# SCH_LucidVR_Proto5_SensorModule_RevB.net
KiCad netlist of a schematic drawn in EasyEDA
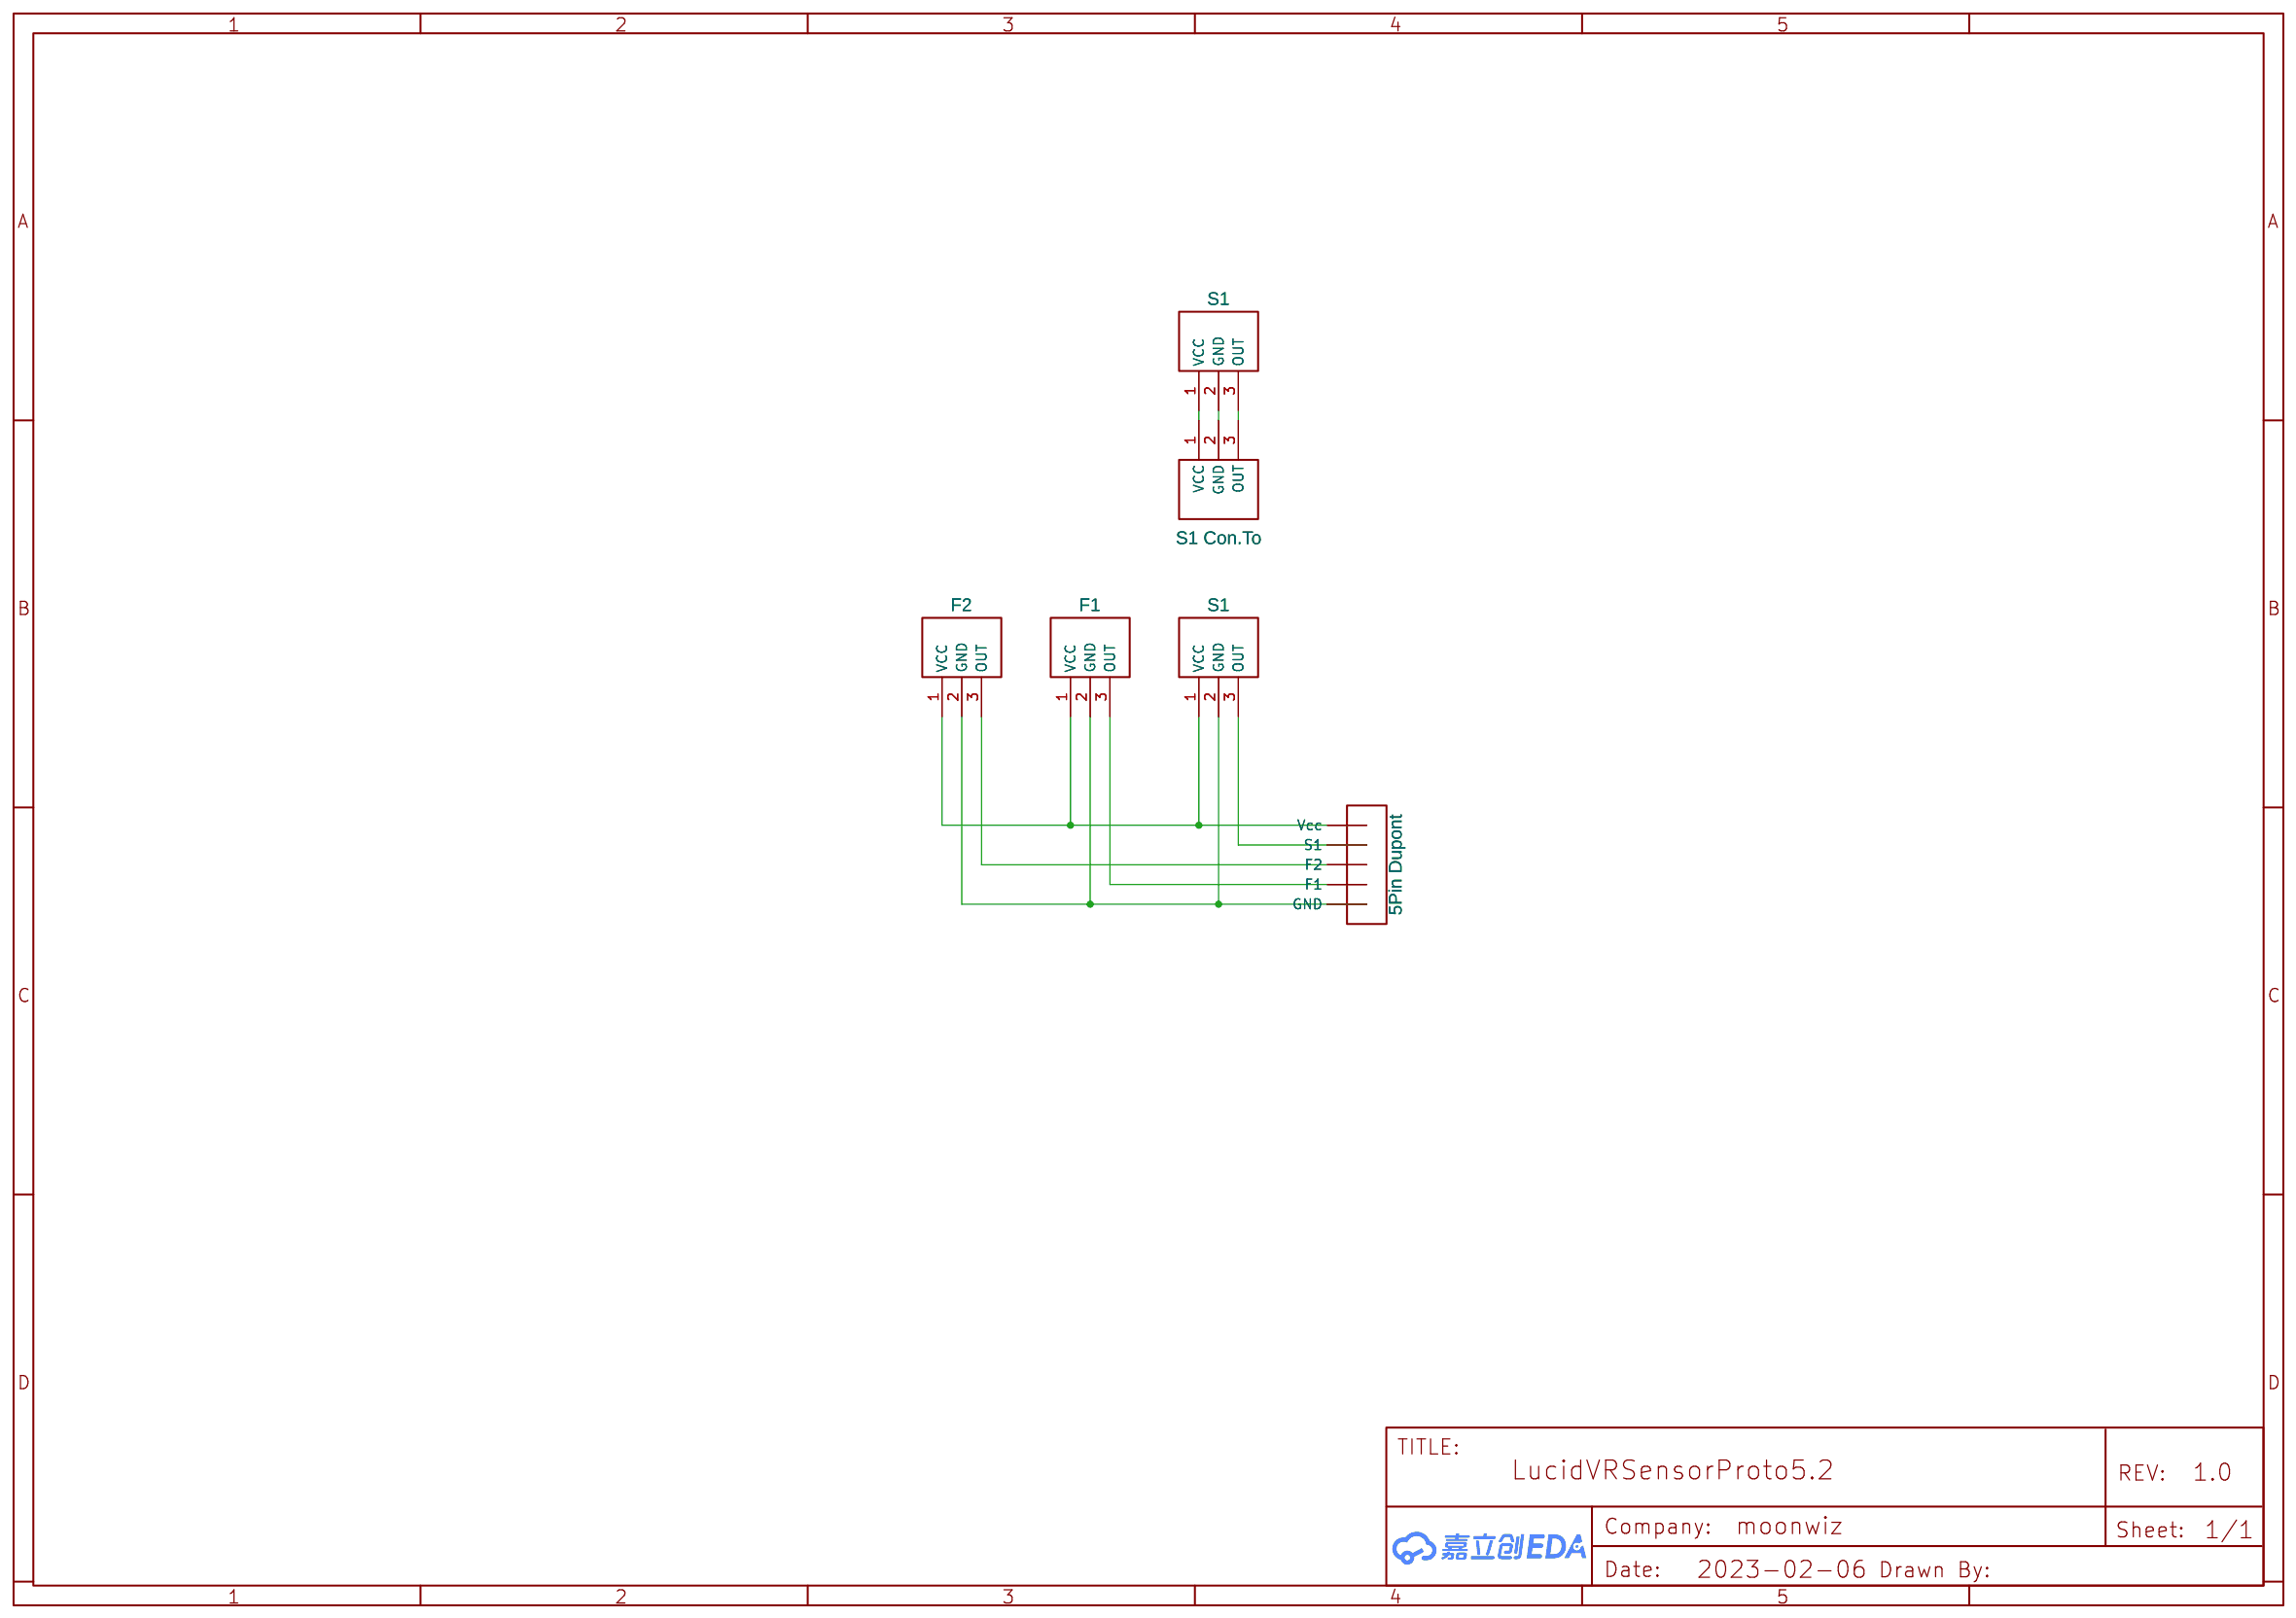
[diagram p0: schematic sheet]

(export (version "E")
  (design (tool "Eeschema 10.0.6"))
  (components
    (comp (ref "S1")
      (value "S1 Con.To")
      (fields (field (name "BOM_Manufacturer Part") "OH49E") (field (name "BOM_Supplier Part") "C81386"))
      (libsource (lib "") (part "OH49E_1"))
    )
    (comp (ref "S2")
      (value "S1")
      (fields (field (name "BOM_Manufacturer Part") "OH49E") (field (name "BOM_Supplier Part") "C81386"))
      (libsource (lib "") (part "OH49E"))
    )
    (comp (ref "S4")
      (value "F1")
      (fields (field (name "BOM_Manufacturer Part") "OH49E") (field (name "BOM_Supplier Part") "C81386"))
      (libsource (lib "") (part "OH49E"))
    )
    (comp (ref "S5")
      (value "S1")
      (fields (field (name "BOM_Manufacturer Part") "OH49E") (field (name "BOM_Supplier Part") "C81386"))
      (libsource (lib "") (part "OH49E"))
    )
    (comp (ref "S6")
      (value "F2")
      (fields (field (name "BOM_Manufacturer Part") "OH49E") (field (name "BOM_Supplier Part") "C81386"))
      (libsource (lib "") (part "OH49E"))
    )
    (comp (ref "U3") (value "5Pin Dupont") (libsource (lib "") (part "5Pin Dupont")))
  )
  (nets
    (net (code "1") (name "Net-(S1-GND)") (class "Default")
      (node (ref "S1") (pin "2") (pinfunction "GND_2") (pintype "unspecified"))
      (node (ref "S5") (pin "2") (pinfunction "GND_2") (pintype "unspecified"))
    )
    (net (code "2") (name "Net-(S1-OUT)") (class "Default")
      (node (ref "S1") (pin "3") (pinfunction "OUT_3") (pintype "unspecified"))
      (node (ref "S5") (pin "3") (pinfunction "OUT_3") (pintype "unspecified"))
    )
    (net (code "3") (name "Net-(S1-VCC)") (class "Default")
      (node (ref "S1") (pin "1") (pinfunction "VCC_1") (pintype "unspecified"))
      (node (ref "S5") (pin "1") (pinfunction "VCC_1") (pintype "unspecified"))
    )
    (net (code "4") (name "Net-(S2-GND)") (class "Default")
      (node (ref "S2") (pin "2") (pinfunction "GND_2") (pintype "unspecified"))
      (node (ref "S4") (pin "2") (pinfunction "GND_2") (pintype "unspecified"))
      (node (ref "S6") (pin "2") (pinfunction "GND_2") (pintype "unspecified"))
      (node (ref "U3") (pin "5") (pinfunction "GND_5") (pintype "unspecified"))
    )
    (net (code "5") (name "Net-(S2-OUT)") (class "Default")
      (node (ref "S2") (pin "3") (pinfunction "OUT_3") (pintype "unspecified"))
      (node (ref "U3") (pin "2") (pinfunction "S1_2") (pintype "unspecified"))
    )
    (net (code "6") (name "Net-(S2-VCC)") (class "Default")
      (node (ref "S2") (pin "1") (pinfunction "VCC_1") (pintype "unspecified"))
      (node (ref "S4") (pin "1") (pinfunction "VCC_1") (pintype "unspecified"))
      (node (ref "S6") (pin "1") (pinfunction "VCC_1") (pintype "unspecified"))
      (node (ref "U3") (pin "1") (pinfunction "Vcc_1") (pintype "unspecified"))
    )
    (net (code "7") (name "Net-(S4-OUT)") (class "Default")
      (node (ref "S4") (pin "3") (pinfunction "OUT_3") (pintype "unspecified"))
      (node (ref "U3") (pin "4") (pinfunction "F1_4") (pintype "unspecified"))
    )
    (net (code "8") (name "Net-(S6-OUT)") (class "Default")
      (node (ref "S6") (pin "3") (pinfunction "OUT_3") (pintype "unspecified"))
      (node (ref "U3") (pin "3") (pinfunction "F2_3") (pintype "unspecified"))
    )
  )
)
